# ValveModule_r2_1.net
KiCad netlist of a schematic drawn in EAGLE
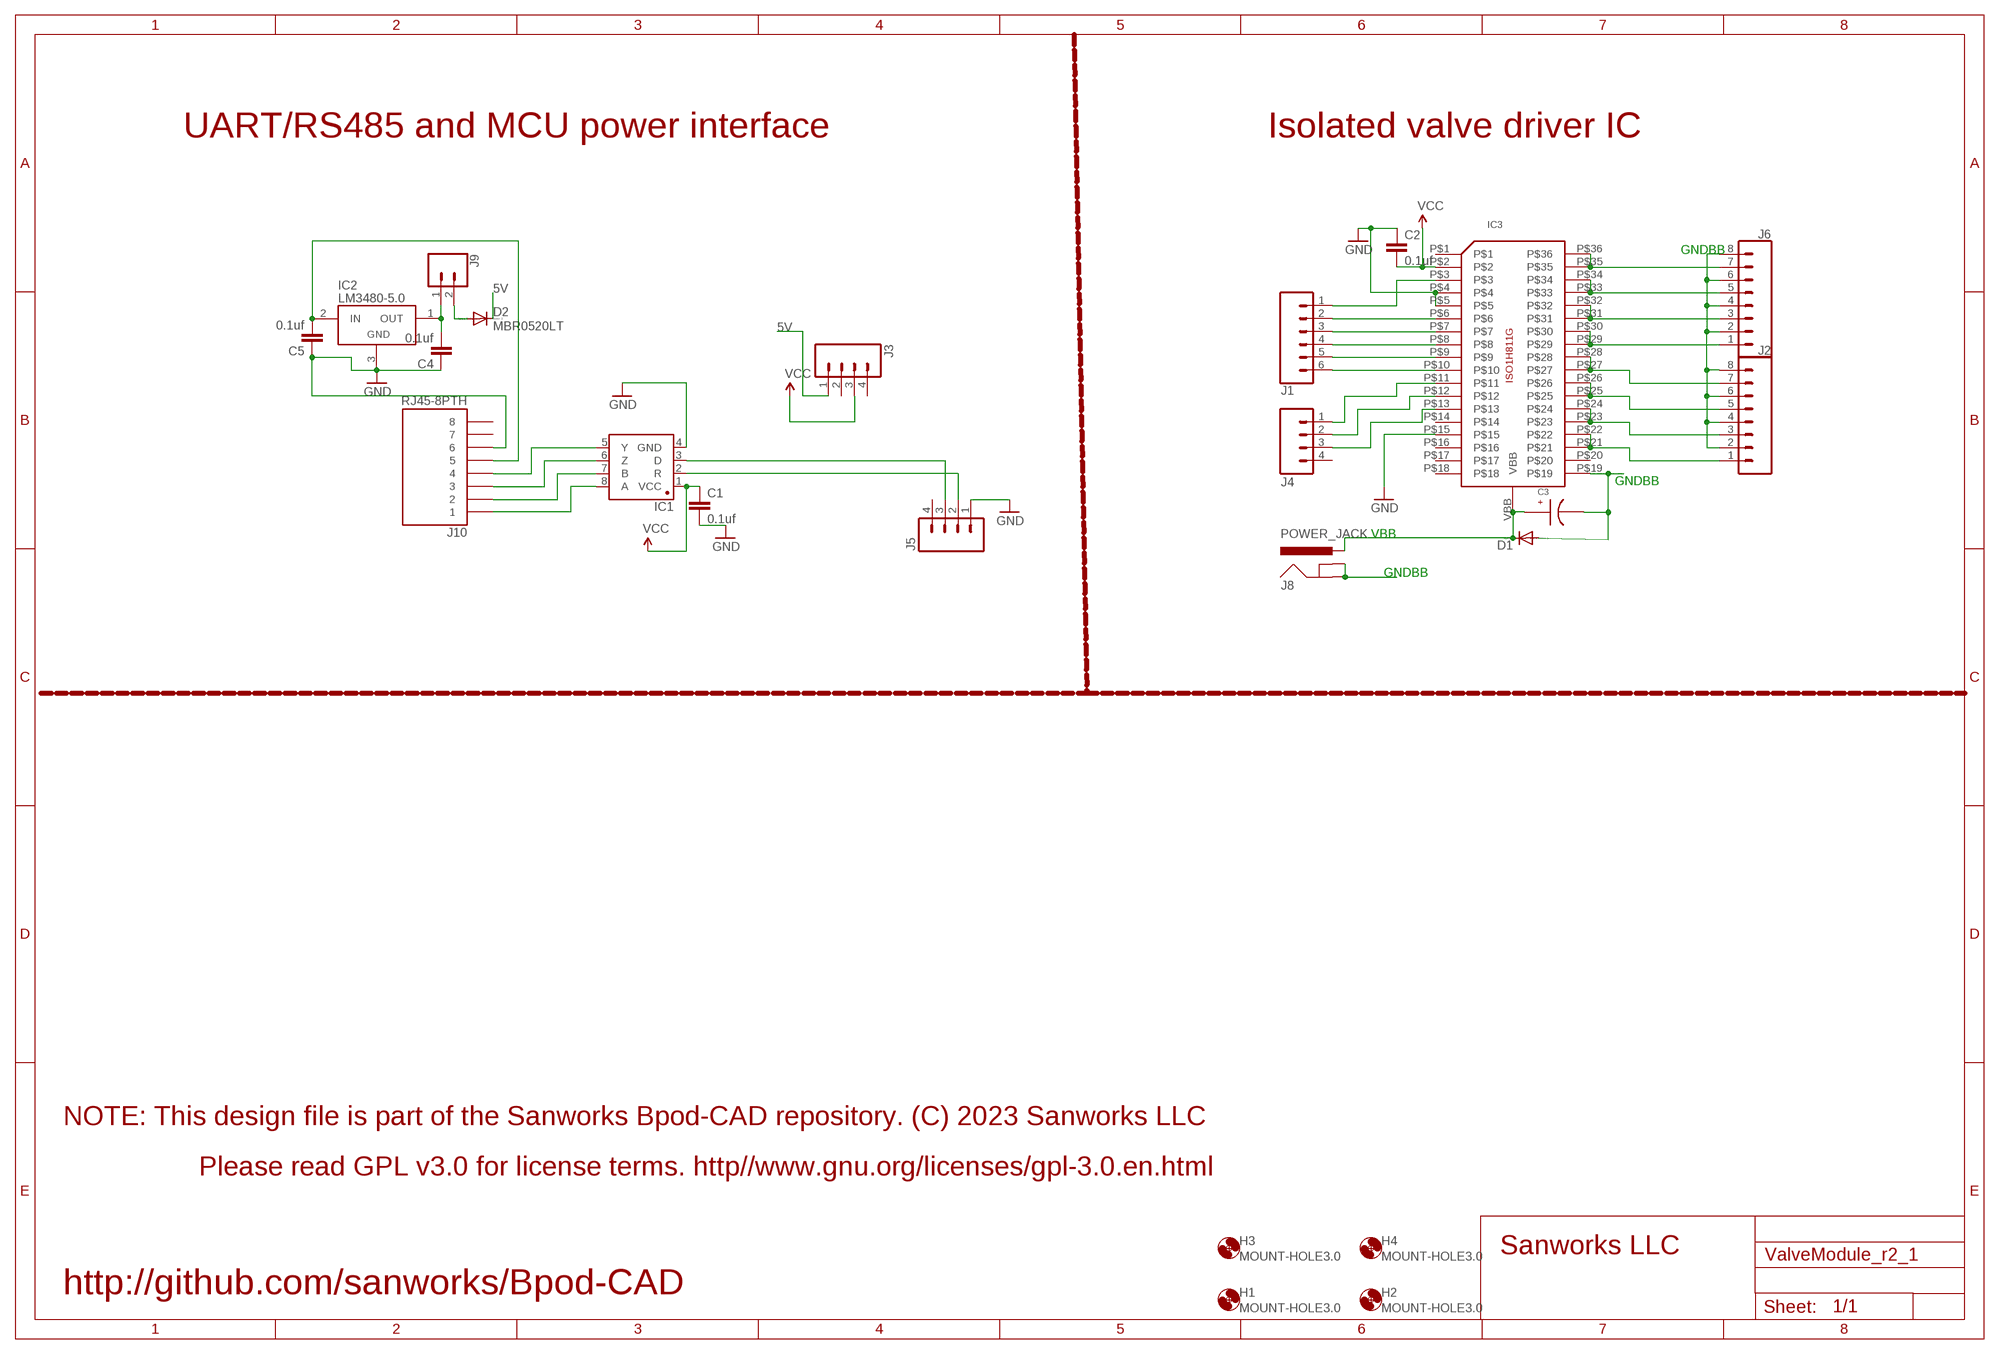
[diagram p0: schematic, sheet 1]

(export (version "E")
  (design (tool "Eeschema 10.0.6"))
  (components
    (comp (ref "C1")
      (value "0.1uf")
      (footprint "eagle-import:1206")
      (libsource (lib "eagle-import") (part "CAP1206"))
    )
    (comp (ref "C2")
      (value "0.1uf")
      (footprint "eagle-import:1206")
      (libsource (lib "eagle-import") (part "CAP1206"))
    )
    (comp (ref "C3")
      (value "EEE-FK1H100UR")
      (footprint "eagle-import:EEE-FK1H100UR")
      (libsource (lib "eagle-import") (part "EEE-FK1H100UR"))
    )
    (comp (ref "C4")
      (value "0.1uf")
      (footprint "eagle-import:1206")
      (libsource (lib "eagle-import") (part "CAP1206"))
    )
    (comp (ref "C5")
      (value "0.1uf")
      (footprint "eagle-import:1206")
      (libsource (lib "eagle-import") (part "CAP1206"))
    )
    (comp (ref "D1")
      (value "DIODE-DO214AA")
      (footprint "eagle-import:DO214AA")
      (libsource (lib "eagle-import") (part "DIODE-DO214AA"))
    )
    (comp (ref "D2")
      (value "MBR0520LT")
      (footprint "eagle-import:SOD123")
      (libsource (lib "eagle-import") (part "MBR0520LT"))
    )
    (comp (ref "H1")
      (value "MOUNT-HOLE3.0")
      (footprint "eagle-import:3,0")
      (libsource (lib "eagle-import") (part "MOUNT-HOLE3.0"))
    )
    (comp (ref "H2")
      (value "MOUNT-HOLE3.0")
      (footprint "eagle-import:3,0")
      (libsource (lib "eagle-import") (part "MOUNT-HOLE3.0"))
    )
    (comp (ref "H3")
      (value "MOUNT-HOLE3.0")
      (footprint "eagle-import:3,0")
      (libsource (lib "eagle-import") (part "MOUNT-HOLE3.0"))
    )
    (comp (ref "H4")
      (value "MOUNT-HOLE3.0")
      (footprint "eagle-import:3,0")
      (libsource (lib "eagle-import") (part "MOUNT-HOLE3.0"))
    )
    (comp (ref "IC1")
      (value "SN65HVD31DR")
      (footprint "eagle-import:SO08")
      (libsource (lib "eagle-import") (part "SN65HVD31DR"))
    )
    (comp (ref "IC2")
      (value "LM3480-5.0")
      (footprint "eagle-import:SOT-23-3")
      (libsource (lib "eagle-import") (part "LM3480-5.0"))
    )
    (comp (ref "IC3")
      (value "ISO1H811G")
      (footprint "eagle-import:ISO1H811G")
      (libsource (lib "eagle-import") (part "ISO1H811G"))
    )
    (comp (ref "J1")
      (value "CONN_06SILK_FEMALE_PTH")
      (footprint "eagle-import:1X06")
      (libsource (lib "eagle-import") (part "CONN_06SILK_FEMALE_PTH"))
    )
    (comp (ref "J2")
      (value "CONN_083.5MM-8")
      (footprint "eagle-import:SCREWTERMINAL-3.5MM-8")
      (libsource (lib "eagle-import") (part "CONN_083.5MM-8"))
    )
    (comp (ref "J3")
      (value "M04PTH")
      (footprint "eagle-import:1X04")
      (libsource (lib "eagle-import") (part "M04PTH"))
    )
    (comp (ref "J4")
      (value "M04PTH")
      (footprint "eagle-import:1X04")
      (libsource (lib "eagle-import") (part "M04PTH"))
    )
    (comp (ref "J5")
      (value "M04PTH")
      (footprint "eagle-import:1X04")
      (libsource (lib "eagle-import") (part "M04PTH"))
    )
    (comp (ref "J6")
      (value "CONN_083.5MM-8")
      (footprint "eagle-import:SCREWTERMINAL-3.5MM-8")
      (libsource (lib "eagle-import") (part "CONN_083.5MM-8"))
    )
    (comp (ref "J8")
      (value "POWER_JACK")
      (footprint "eagle-import:POWER_JACK_PTH")
      (libsource (lib "eagle-import") (part "POWER_JACK"))
    )
    (comp (ref "J9")
      (value "CONN_02")
      (footprint "eagle-import:1X02")
      (libsource (lib "eagle-import") (part "CONN_02"))
    )
    (comp (ref "J10")
      (value "RJ45-8PTH")
      (footprint "eagle-import:RJ45-8")
      (libsource (lib "eagle-import") (part "RJ45-8PTH"))
    )
  )
  (nets
    (net (code "1") (name "/5V") (class "Default")
      (node (ref "D2") (pin "C") (pinfunction "C_C") (pintype "passive"))
      (node (ref "J3") (pin "1") (pinfunction "1_1") (pintype "passive"))
    )
    (net (code "2") (name "/GNDBB") (class "Default")
      (node (ref "C3") (pin "CATHODE") (pinfunction "CATHODE_CATHODE") (pintype "bidirectional"))
      (node (ref "D1") (pin "A") (pinfunction "A_A") (pintype "passive"))
      (node (ref "IC3") (pin "P$19") (pinfunction "P$19_P$19") (pintype "bidirectional"))
      (node (ref "J2") (pin "2") (pinfunction "2_2") (pintype "passive"))
      (node (ref "J2") (pin "4") (pinfunction "4_4") (pintype "passive"))
      (node (ref "J2") (pin "6") (pinfunction "6_6") (pintype "passive"))
      (node (ref "J2") (pin "8") (pinfunction "8_8") (pintype "passive"))
      (node (ref "J6") (pin "2") (pinfunction "2_2") (pintype "passive"))
      (node (ref "J6") (pin "4") (pinfunction "4_4") (pintype "passive"))
      (node (ref "J6") (pin "6") (pinfunction "6_6") (pintype "passive"))
      (node (ref "J6") (pin "8") (pinfunction "8_8") (pintype "passive"))
      (node (ref "J8") (pin "GND") (pinfunction "GND_GND") (pintype "bidirectional"))
      (node (ref "J8") (pin "GNDBREAK") (pinfunction "GNDBREAK_GNDBREAK") (pintype "bidirectional"))
    )
    (net (code "3") (name "GND") (class "Default")
      (node (ref "C1") (pin "2") (pinfunction "2_2") (pintype "passive"))
      (node (ref "C2") (pin "1") (pinfunction "1_1") (pintype "passive"))
      (node (ref "C4") (pin "1") (pinfunction "1_1") (pintype "passive"))
      (node (ref "C5") (pin "1") (pinfunction "1_1") (pintype "passive"))
      (node (ref "IC1") (pin "4") (pinfunction "GND_4") (pintype "bidirectional"))
      (node (ref "IC2") (pin "3") (pinfunction "GND_3") (pintype "power_in"))
      (node (ref "IC3") (pin "P$15") (pinfunction "P$15_P$15") (pintype "bidirectional"))
      (node (ref "IC3") (pin "P$4") (pinfunction "P$4_P$4") (pintype "bidirectional"))
      (node (ref "IC3") (pin "P$5") (pinfunction "P$5_P$5") (pintype "bidirectional"))
      (node (ref "J10") (pin "6") (pinfunction "6_6") (pintype "bidirectional"))
      (node (ref "J5") (pin "1") (pinfunction "1_1") (pintype "passive"))
    )
    (net (code "4") (name "Net-(C3-PadANODE)") (class "Default")
      (node (ref "C3") (pin "ANODE") (pinfunction "ANODE_ANODE") (pintype "bidirectional"))
      (node (ref "D1") (pin "C") (pinfunction "C_C") (pintype "passive"))
      (node (ref "IC3") (pin "VBB") (pinfunction "VBB_VBB") (pintype "bidirectional"))
      (node (ref "J8") (pin "PWR") (pinfunction "PWR_PWR") (pintype "bidirectional"))
    )
    (net (code "5") (name "Net-(D2-PadA)") (class "Default")
      (node (ref "D2") (pin "A") (pinfunction "A_A") (pintype "passive"))
      (node (ref "J9") (pin "2") (pinfunction "2_2") (pintype "passive"))
    )
    (net (code "6") (name "Net-(IC1-A)") (class "Default")
      (node (ref "IC1") (pin "8") (pinfunction "A_8") (pintype "bidirectional"))
      (node (ref "J10") (pin "1") (pinfunction "1_1") (pintype "bidirectional"))
    )
    (net (code "7") (name "Net-(IC1-B)") (class "Default")
      (node (ref "IC1") (pin "7") (pinfunction "B_7") (pintype "bidirectional"))
      (node (ref "J10") (pin "2") (pinfunction "2_2") (pintype "bidirectional"))
    )
    (net (code "8") (name "Net-(IC1-D)") (class "Default")
      (node (ref "IC1") (pin "3") (pinfunction "D_3") (pintype "bidirectional"))
      (node (ref "J5") (pin "3") (pinfunction "3_3") (pintype "passive"))
    )
    (net (code "9") (name "Net-(IC1-R)") (class "Default")
      (node (ref "IC1") (pin "2") (pinfunction "R_2") (pintype "bidirectional"))
      (node (ref "J5") (pin "2") (pinfunction "2_2") (pintype "passive"))
    )
    (net (code "10") (name "Net-(IC1-Y)") (class "Default")
      (node (ref "IC1") (pin "5") (pinfunction "Y_5") (pintype "bidirectional"))
      (node (ref "J10") (pin "4") (pinfunction "4_4") (pintype "bidirectional"))
    )
    (net (code "11") (name "Net-(IC1-Z)") (class "Default")
      (node (ref "IC1") (pin "6") (pinfunction "Z_6") (pintype "bidirectional"))
      (node (ref "J10") (pin "3") (pinfunction "3_3") (pintype "bidirectional"))
    )
    (net (code "12") (name "Net-(IC2-IN)") (class "Default")
      (node (ref "C5") (pin "2") (pinfunction "2_2") (pintype "passive"))
      (node (ref "IC2") (pin "2") (pinfunction "IN_2") (pintype "power_in"))
      (node (ref "J10") (pin "5") (pinfunction "5_5") (pintype "bidirectional"))
    )
    (net (code "13") (name "Net-(IC2-OUT)") (class "Default")
      (node (ref "C4") (pin "2") (pinfunction "2_2") (pintype "passive"))
      (node (ref "IC2") (pin "1") (pinfunction "OUT_1") (pintype "power_in"))
      (node (ref "J9") (pin "1") (pinfunction "1_1") (pintype "passive"))
    )
    (net (code "14") (name "Net-(IC3-PadP$3)") (class "Default")
      (node (ref "IC3") (pin "P$3") (pinfunction "P$3_P$3") (pintype "bidirectional"))
      (node (ref "J1") (pin "1") (pinfunction "1_1") (pintype "passive"))
    )
    (net (code "15") (name "Net-(IC3-PadP$6)") (class "Default")
      (node (ref "IC3") (pin "P$6") (pinfunction "P$6_P$6") (pintype "bidirectional"))
      (node (ref "J1") (pin "2") (pinfunction "2_2") (pintype "passive"))
    )
    (net (code "16") (name "Net-(IC3-PadP$7)") (class "Default")
      (node (ref "IC3") (pin "P$7") (pinfunction "P$7_P$7") (pintype "bidirectional"))
      (node (ref "J1") (pin "3") (pinfunction "3_3") (pintype "passive"))
    )
    (net (code "17") (name "Net-(IC3-PadP$8)") (class "Default")
      (node (ref "IC3") (pin "P$8") (pinfunction "P$8_P$8") (pintype "bidirectional"))
      (node (ref "J1") (pin "4") (pinfunction "4_4") (pintype "passive"))
    )
    (net (code "18") (name "Net-(IC3-PadP$9)") (class "Default")
      (node (ref "IC3") (pin "P$9") (pinfunction "P$9_P$9") (pintype "bidirectional"))
      (node (ref "J1") (pin "5") (pinfunction "5_5") (pintype "passive"))
    )
    (net (code "19") (name "Net-(IC3-PadP$10)") (class "Default")
      (node (ref "IC3") (pin "P$10") (pinfunction "P$10_P$10") (pintype "bidirectional"))
      (node (ref "J1") (pin "6") (pinfunction "6_6") (pintype "passive"))
    )
    (net (code "20") (name "Net-(IC3-PadP$11)") (class "Default")
      (node (ref "IC3") (pin "P$11") (pinfunction "P$11_P$11") (pintype "bidirectional"))
      (node (ref "J4") (pin "1") (pinfunction "1_1") (pintype "passive"))
    )
    (net (code "21") (name "Net-(IC3-PadP$12)") (class "Default")
      (node (ref "IC3") (pin "P$12") (pinfunction "P$12_P$12") (pintype "bidirectional"))
      (node (ref "J4") (pin "2") (pinfunction "2_2") (pintype "passive"))
    )
    (net (code "22") (name "Net-(IC3-PadP$13)") (class "Default")
      (node (ref "IC3") (pin "P$13") (pinfunction "P$13_P$13") (pintype "bidirectional"))
      (node (ref "J4") (pin "3") (pinfunction "3_3") (pintype "passive"))
    )
    (net (code "23") (name "Net-(IC3-PadP$21)") (class "Default")
      (node (ref "IC3") (pin "P$21") (pinfunction "P$21_P$21") (pintype "bidirectional"))
      (node (ref "IC3") (pin "P$22") (pinfunction "P$22_P$22") (pintype "bidirectional"))
      (node (ref "J2") (pin "1") (pinfunction "1_1") (pintype "passive"))
    )
    (net (code "24") (name "Net-(IC3-PadP$23)") (class "Default")
      (node (ref "IC3") (pin "P$23") (pinfunction "P$23_P$23") (pintype "bidirectional"))
      (node (ref "IC3") (pin "P$24") (pinfunction "P$24_P$24") (pintype "bidirectional"))
      (node (ref "J2") (pin "3") (pinfunction "3_3") (pintype "passive"))
    )
    (net (code "25") (name "Net-(IC3-PadP$25)") (class "Default")
      (node (ref "IC3") (pin "P$25") (pinfunction "P$25_P$25") (pintype "bidirectional"))
      (node (ref "IC3") (pin "P$26") (pinfunction "P$26_P$26") (pintype "bidirectional"))
      (node (ref "J2") (pin "5") (pinfunction "5_5") (pintype "passive"))
    )
    (net (code "26") (name "Net-(IC3-PadP$27)") (class "Default")
      (node (ref "IC3") (pin "P$27") (pinfunction "P$27_P$27") (pintype "bidirectional"))
      (node (ref "IC3") (pin "P$28") (pinfunction "P$28_P$28") (pintype "bidirectional"))
      (node (ref "J2") (pin "7") (pinfunction "7_7") (pintype "passive"))
    )
    (net (code "27") (name "Net-(IC3-PadP$29)") (class "Default")
      (node (ref "IC3") (pin "P$29") (pinfunction "P$29_P$29") (pintype "bidirectional"))
      (node (ref "IC3") (pin "P$30") (pinfunction "P$30_P$30") (pintype "bidirectional"))
      (node (ref "J6") (pin "1") (pinfunction "1_1") (pintype "passive"))
    )
    (net (code "28") (name "Net-(IC3-PadP$31)") (class "Default")
      (node (ref "IC3") (pin "P$31") (pinfunction "P$31_P$31") (pintype "bidirectional"))
      (node (ref "IC3") (pin "P$32") (pinfunction "P$32_P$32") (pintype "bidirectional"))
      (node (ref "J6") (pin "3") (pinfunction "3_3") (pintype "passive"))
    )
    (net (code "29") (name "Net-(IC3-PadP$33)") (class "Default")
      (node (ref "IC3") (pin "P$33") (pinfunction "P$33_P$33") (pintype "bidirectional"))
      (node (ref "IC3") (pin "P$34") (pinfunction "P$34_P$34") (pintype "bidirectional"))
      (node (ref "J6") (pin "5") (pinfunction "5_5") (pintype "passive"))
    )
    (net (code "30") (name "Net-(IC3-PadP$35)") (class "Default")
      (node (ref "IC3") (pin "P$35") (pinfunction "P$35_P$35") (pintype "bidirectional"))
      (node (ref "IC3") (pin "P$36") (pinfunction "P$36_P$36") (pintype "bidirectional"))
      (node (ref "J6") (pin "7") (pinfunction "7_7") (pintype "passive"))
    )
    (net (code "31") (name "VCC") (class "Default")
      (node (ref "C1") (pin "1") (pinfunction "1_1") (pintype "passive"))
      (node (ref "C2") (pin "2") (pinfunction "2_2") (pintype "passive"))
      (node (ref "IC1") (pin "1") (pinfunction "VCC_1") (pintype "bidirectional"))
      (node (ref "IC3") (pin "P$2") (pinfunction "P$2_P$2") (pintype "bidirectional"))
      (node (ref "J3") (pin "3") (pinfunction "3_3") (pintype "passive"))
    )
    (net (code "32") (name "unconnected-(IC3-PadP$1)") (class "Default")
      (node (ref "IC3") (pin "P$1") (pinfunction "P$1_P$1") (pintype "bidirectional"))
    )
    (net (code "33") (name "unconnected-(IC3-PadP$14)") (class "Default")
      (node (ref "IC3") (pin "P$14") (pinfunction "P$14_P$14") (pintype "bidirectional"))
    )
    (net (code "34") (name "unconnected-(IC3-PadP$16)") (class "Default")
      (node (ref "IC3") (pin "P$16") (pinfunction "P$16_P$16") (pintype "bidirectional"))
    )
    (net (code "35") (name "unconnected-(IC3-PadP$17)") (class "Default")
      (node (ref "IC3") (pin "P$17") (pinfunction "P$17_P$17") (pintype "bidirectional"))
    )
    (net (code "36") (name "unconnected-(IC3-PadP$18)") (class "Default")
      (node (ref "IC3") (pin "P$18") (pinfunction "P$18_P$18") (pintype "bidirectional"))
    )
    (net (code "37") (name "unconnected-(IC3-PadP$20)") (class "Default")
      (node (ref "IC3") (pin "P$20") (pinfunction "P$20_P$20") (pintype "bidirectional"))
    )
    (net (code "38") (name "unconnected-(J3-Pad2)") (class "Default")
      (node (ref "J3") (pin "2") (pinfunction "2_2") (pintype "passive"))
    )
    (net (code "39") (name "unconnected-(J3-Pad4)") (class "Default")
      (node (ref "J3") (pin "4") (pinfunction "4_4") (pintype "passive"))
    )
    (net (code "40") (name "unconnected-(J4-Pad4)") (class "Default")
      (node (ref "J4") (pin "4") (pinfunction "4_4") (pintype "passive"))
    )
    (net (code "41") (name "unconnected-(J5-Pad4)") (class "Default")
      (node (ref "J5") (pin "4") (pinfunction "4_4") (pintype "passive"))
    )
    (net (code "42") (name "unconnected-(J10-Pad7)") (class "Default")
      (node (ref "J10") (pin "7") (pinfunction "7_7") (pintype "bidirectional"))
    )
    (net (code "43") (name "unconnected-(J10-Pad8)") (class "Default")
      (node (ref "J10") (pin "8") (pinfunction "8_8") (pintype "bidirectional"))
    )
  )
)
